# OpAmpBreakout-fragmentB.net
KiCad netlist of a schematic drawn in EAGLE
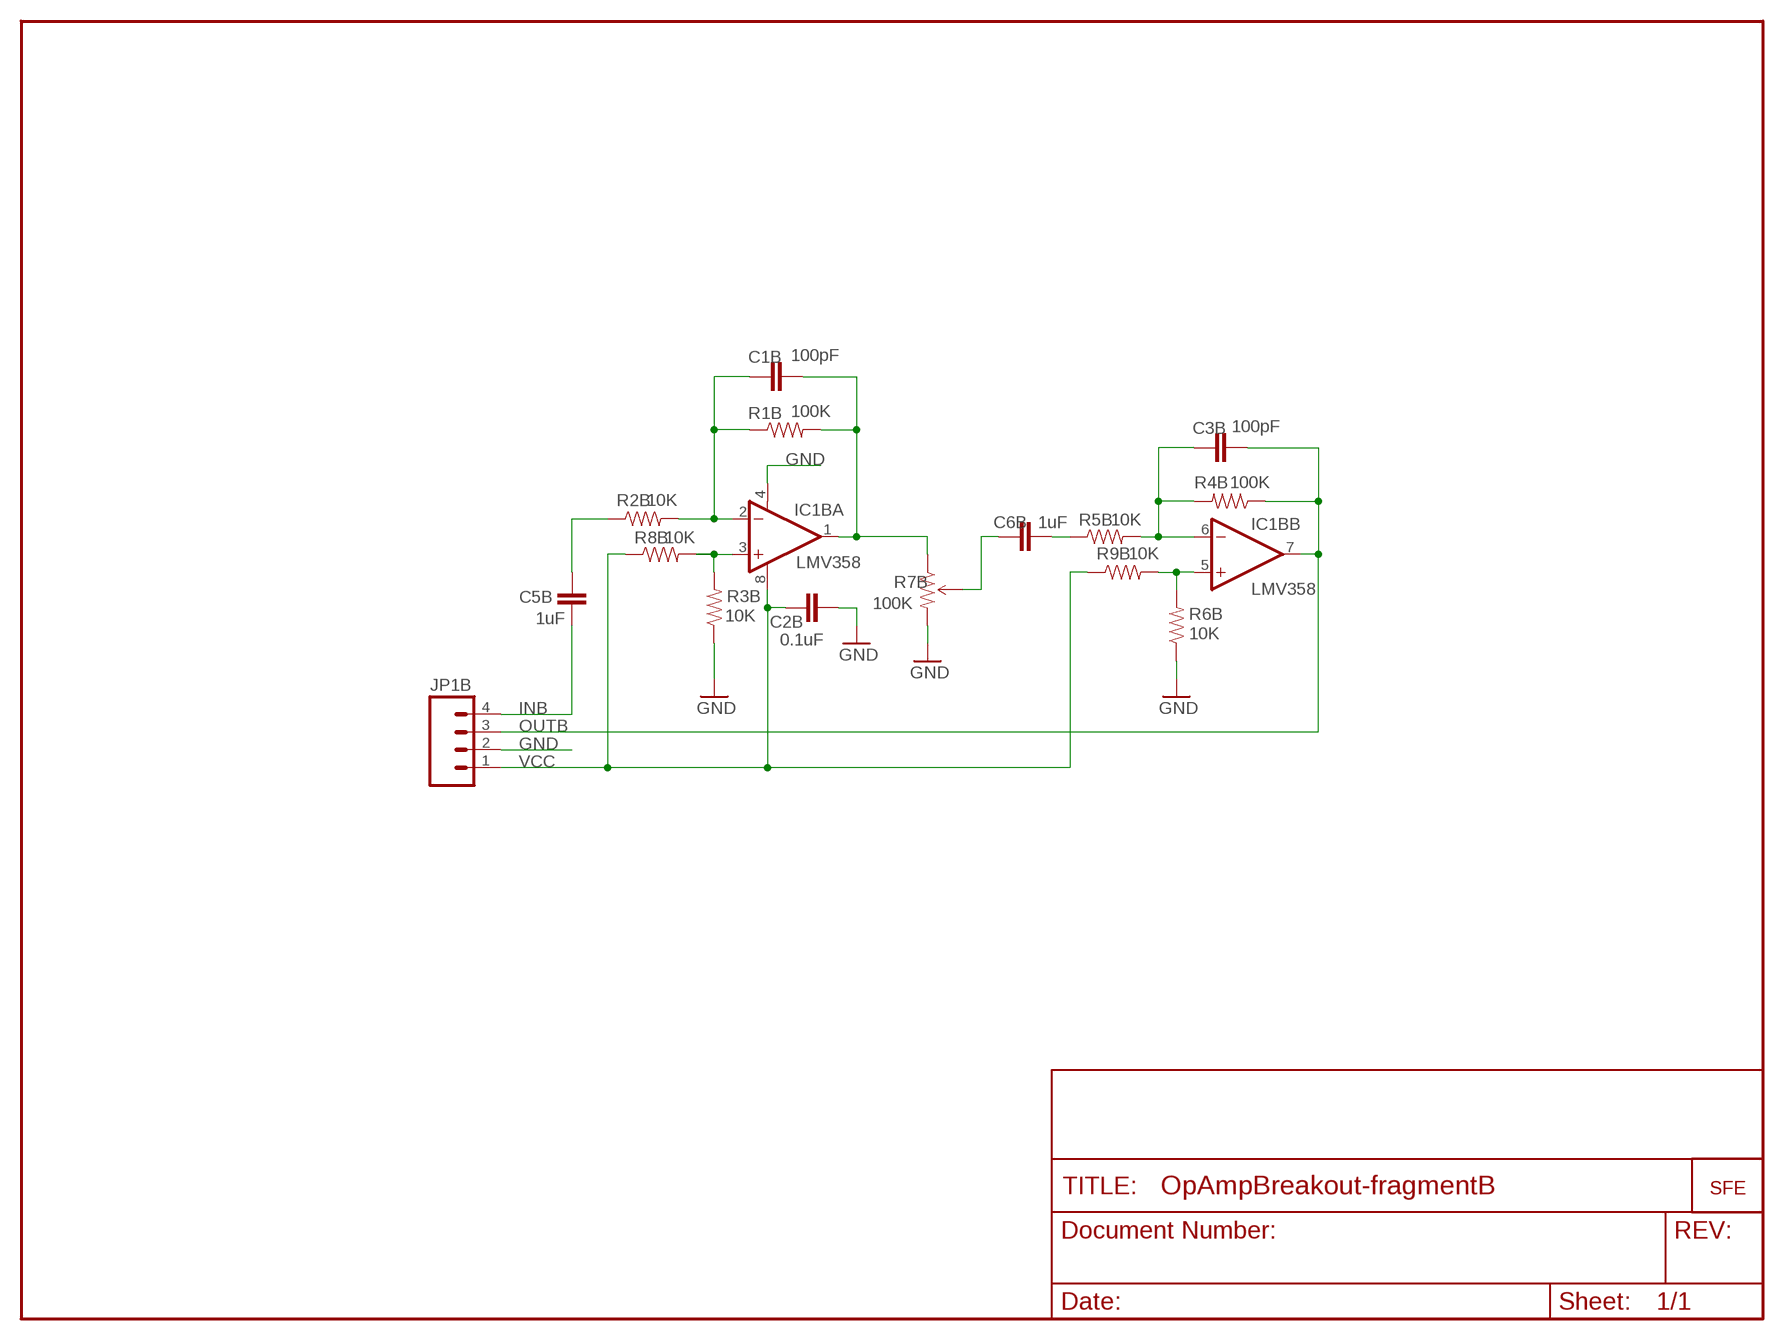
[diagram p0: schematic, sheet 1]

(export (version "E")
  (design (tool "Eeschema 10.0.6"))
  (components
    (comp (ref "C1B")
      (value "100pF")
      (footprint "eagle-import:C0402")
      (libsource (lib "eagle-import") (part "CAP0402"))
    )
    (comp (ref "C2B")
      (value "0.1uF")
      (footprint "eagle-import:C0402")
      (libsource (lib "eagle-import") (part "CAP0402"))
    )
    (comp (ref "C3B")
      (value "100pF")
      (footprint "eagle-import:C0402")
      (libsource (lib "eagle-import") (part "CAP0402"))
    )
    (comp (ref "C5B")
      (value "1uF")
      (footprint "eagle-import:C0402")
      (libsource (lib "eagle-import") (part "CAP0402"))
    )
    (comp (ref "C6B")
      (value "1uF")
      (footprint "eagle-import:C0402")
      (libsource (lib "eagle-import") (part "CAP0402"))
    )
    (comp (ref "IC1B")
      (value "LMV358")
      (footprint "eagle-import:SO08")
      (libsource (lib "eagle-import") (part "OPAMP-DUALU"))
    )
    (comp (ref "JP1B")
      (value "M04PTH")
      (footprint "eagle-import:1X04")
      (libsource (lib "eagle-import") (part "M04PTH"))
    )
    (comp (ref "R1B")
      (value "100K")
      (footprint "eagle-import:C0402")
      (libsource (lib "eagle-import") (part "RESISTOR0402"))
    )
    (comp (ref "R2B")
      (value "10K")
      (footprint "eagle-import:C0402")
      (libsource (lib "eagle-import") (part "RESISTOR0402"))
    )
    (comp (ref "R3B")
      (value "10K")
      (footprint "eagle-import:C0402")
      (libsource (lib "eagle-import") (part "RESISTOR0402"))
    )
    (comp (ref "R4B")
      (value "100K")
      (footprint "eagle-import:C0402")
      (libsource (lib "eagle-import") (part "RESISTOR0402"))
    )
    (comp (ref "R5B")
      (value "10K")
      (footprint "eagle-import:C0402")
      (libsource (lib "eagle-import") (part "RESISTOR0402"))
    )
    (comp (ref "R6B")
      (value "10K")
      (footprint "eagle-import:C0402")
      (libsource (lib "eagle-import") (part "RESISTOR0402"))
    )
    (comp (ref "R7B")
      (value "100K")
      (footprint "eagle-import:TRIMPOT-3MM")
      (libsource (lib "eagle-import") (part "TRIMPOTSMD"))
    )
    (comp (ref "R8B")
      (value "10K")
      (footprint "eagle-import:C0402")
      (libsource (lib "eagle-import") (part "SparkFun-DC_RESISTOR0402"))
    )
    (comp (ref "R9B")
      (value "10K")
      (footprint "eagle-import:C0402")
      (libsource (lib "eagle-import") (part "SparkFun-DC_RESISTOR0402"))
    )
    (comp (ref "U$3B")
      (value "LOGO-SFENEW")
      (footprint "eagle-import:SFE-NEW-WEBLOGO")
      (libsource (lib "eagle-import") (part "LOGO-SFENEW"))
    )
  )
  (nets
    (net (code "1") (name "/INB") (class "Default")
      (node (ref "C5B") (pin "1") (pinfunction "1_1") (pintype "passive"))
      (node (ref "JP1B") (pin "4") (pinfunction "4_4") (pintype "passive"))
    )
    (net (code "2") (name "/OUTB") (class "Default")
      (node (ref "C3B") (pin "2") (pinfunction "2_2") (pintype "passive"))
      (node (ref "IC1B") (pin "7") (pinfunction "OUT_7") (pintype "output"))
      (node (ref "JP1B") (pin "3") (pinfunction "3_3") (pintype "passive"))
      (node (ref "R4B") (pin "1") (pinfunction "1_1") (pintype "passive"))
    )
    (net (code "3") (name "/VCC") (class "Default")
      (node (ref "C2B") (pin "1") (pinfunction "1_1") (pintype "passive"))
      (node (ref "IC1B") (pin "8") (pinfunction "V+_8") (pintype "power_in"))
      (node (ref "JP1B") (pin "1") (pinfunction "1_1") (pintype "passive"))
      (node (ref "R8B") (pin "1") (pinfunction "1_1") (pintype "passive"))
      (node (ref "R9B") (pin "1") (pinfunction "1_1") (pintype "passive"))
    )
    (net (code "4") (name "GND") (class "Default")
      (node (ref "C2B") (pin "2") (pinfunction "2_2") (pintype "passive"))
      (node (ref "IC1B") (pin "4") (pinfunction "V-_4") (pintype "power_in"))
      (node (ref "JP1B") (pin "2") (pinfunction "2_2") (pintype "passive"))
      (node (ref "R3B") (pin "1") (pinfunction "1_1") (pintype "passive"))
      (node (ref "R6B") (pin "1") (pinfunction "1_1") (pintype "passive"))
      (node (ref "R7B") (pin "3") (pinfunction "CW_3") (pintype "passive"))
    )
    (net (code "5") (name "Net-(C5B-Pad2)") (class "Default")
      (node (ref "C5B") (pin "2") (pinfunction "2_2") (pintype "passive"))
      (node (ref "R2B") (pin "1") (pinfunction "1_1") (pintype "passive"))
    )
    (net (code "6") (name "Net-(C6B-Pad1)") (class "Default")
      (node (ref "C6B") (pin "1") (pinfunction "1_1") (pintype "passive"))
      (node (ref "R5B") (pin "1") (pinfunction "1_1") (pintype "passive"))
    )
    (net (code "7") (name "Net-(IC1BA-+IN)") (class "Default")
      (node (ref "IC1B") (pin "3") (pinfunction "+IN_3") (pintype "input"))
      (node (ref "R3B") (pin "2") (pinfunction "2_2") (pintype "passive"))
      (node (ref "R8B") (pin "2") (pinfunction "2_2") (pintype "passive"))
    )
    (net (code "8") (name "Net-(IC1BA--IN)") (class "Default")
      (node (ref "C1B") (pin "1") (pinfunction "1_1") (pintype "passive"))
      (node (ref "IC1B") (pin "2") (pinfunction "-IN_2") (pintype "input"))
      (node (ref "R1B") (pin "1") (pinfunction "1_1") (pintype "passive"))
      (node (ref "R2B") (pin "2") (pinfunction "2_2") (pintype "passive"))
    )
    (net (code "9") (name "Net-(IC1BA-OUT)") (class "Default")
      (node (ref "C1B") (pin "2") (pinfunction "2_2") (pintype "passive"))
      (node (ref "IC1B") (pin "1") (pinfunction "OUT_1") (pintype "output"))
      (node (ref "R1B") (pin "2") (pinfunction "2_2") (pintype "passive"))
      (node (ref "R7B") (pin "1") (pinfunction "CCW_1") (pintype "passive"))
    )
    (net (code "10") (name "Net-(IC1BB-+IN)") (class "Default")
      (node (ref "IC1B") (pin "5") (pinfunction "+IN_5") (pintype "input"))
      (node (ref "R6B") (pin "2") (pinfunction "2_2") (pintype "passive"))
      (node (ref "R9B") (pin "2") (pinfunction "2_2") (pintype "passive"))
    )
    (net (code "11") (name "Net-(IC1BB--IN)") (class "Default")
      (node (ref "C3B") (pin "1") (pinfunction "1_1") (pintype "passive"))
      (node (ref "IC1B") (pin "6") (pinfunction "-IN_6") (pintype "input"))
      (node (ref "R4B") (pin "2") (pinfunction "2_2") (pintype "passive"))
      (node (ref "R5B") (pin "2") (pinfunction "2_2") (pintype "passive"))
    )
    (net (code "12") (name "Net-(R7B-WIPER)") (class "Default")
      (node (ref "C6B") (pin "2") (pinfunction "2_2") (pintype "passive"))
      (node (ref "R7B") (pin "2") (pinfunction "WIPER_2") (pintype "passive"))
    )
  )
)
